# mach_xa_pin_schematic.net
KiCad netlist of a schematic drawn in Altium Designer
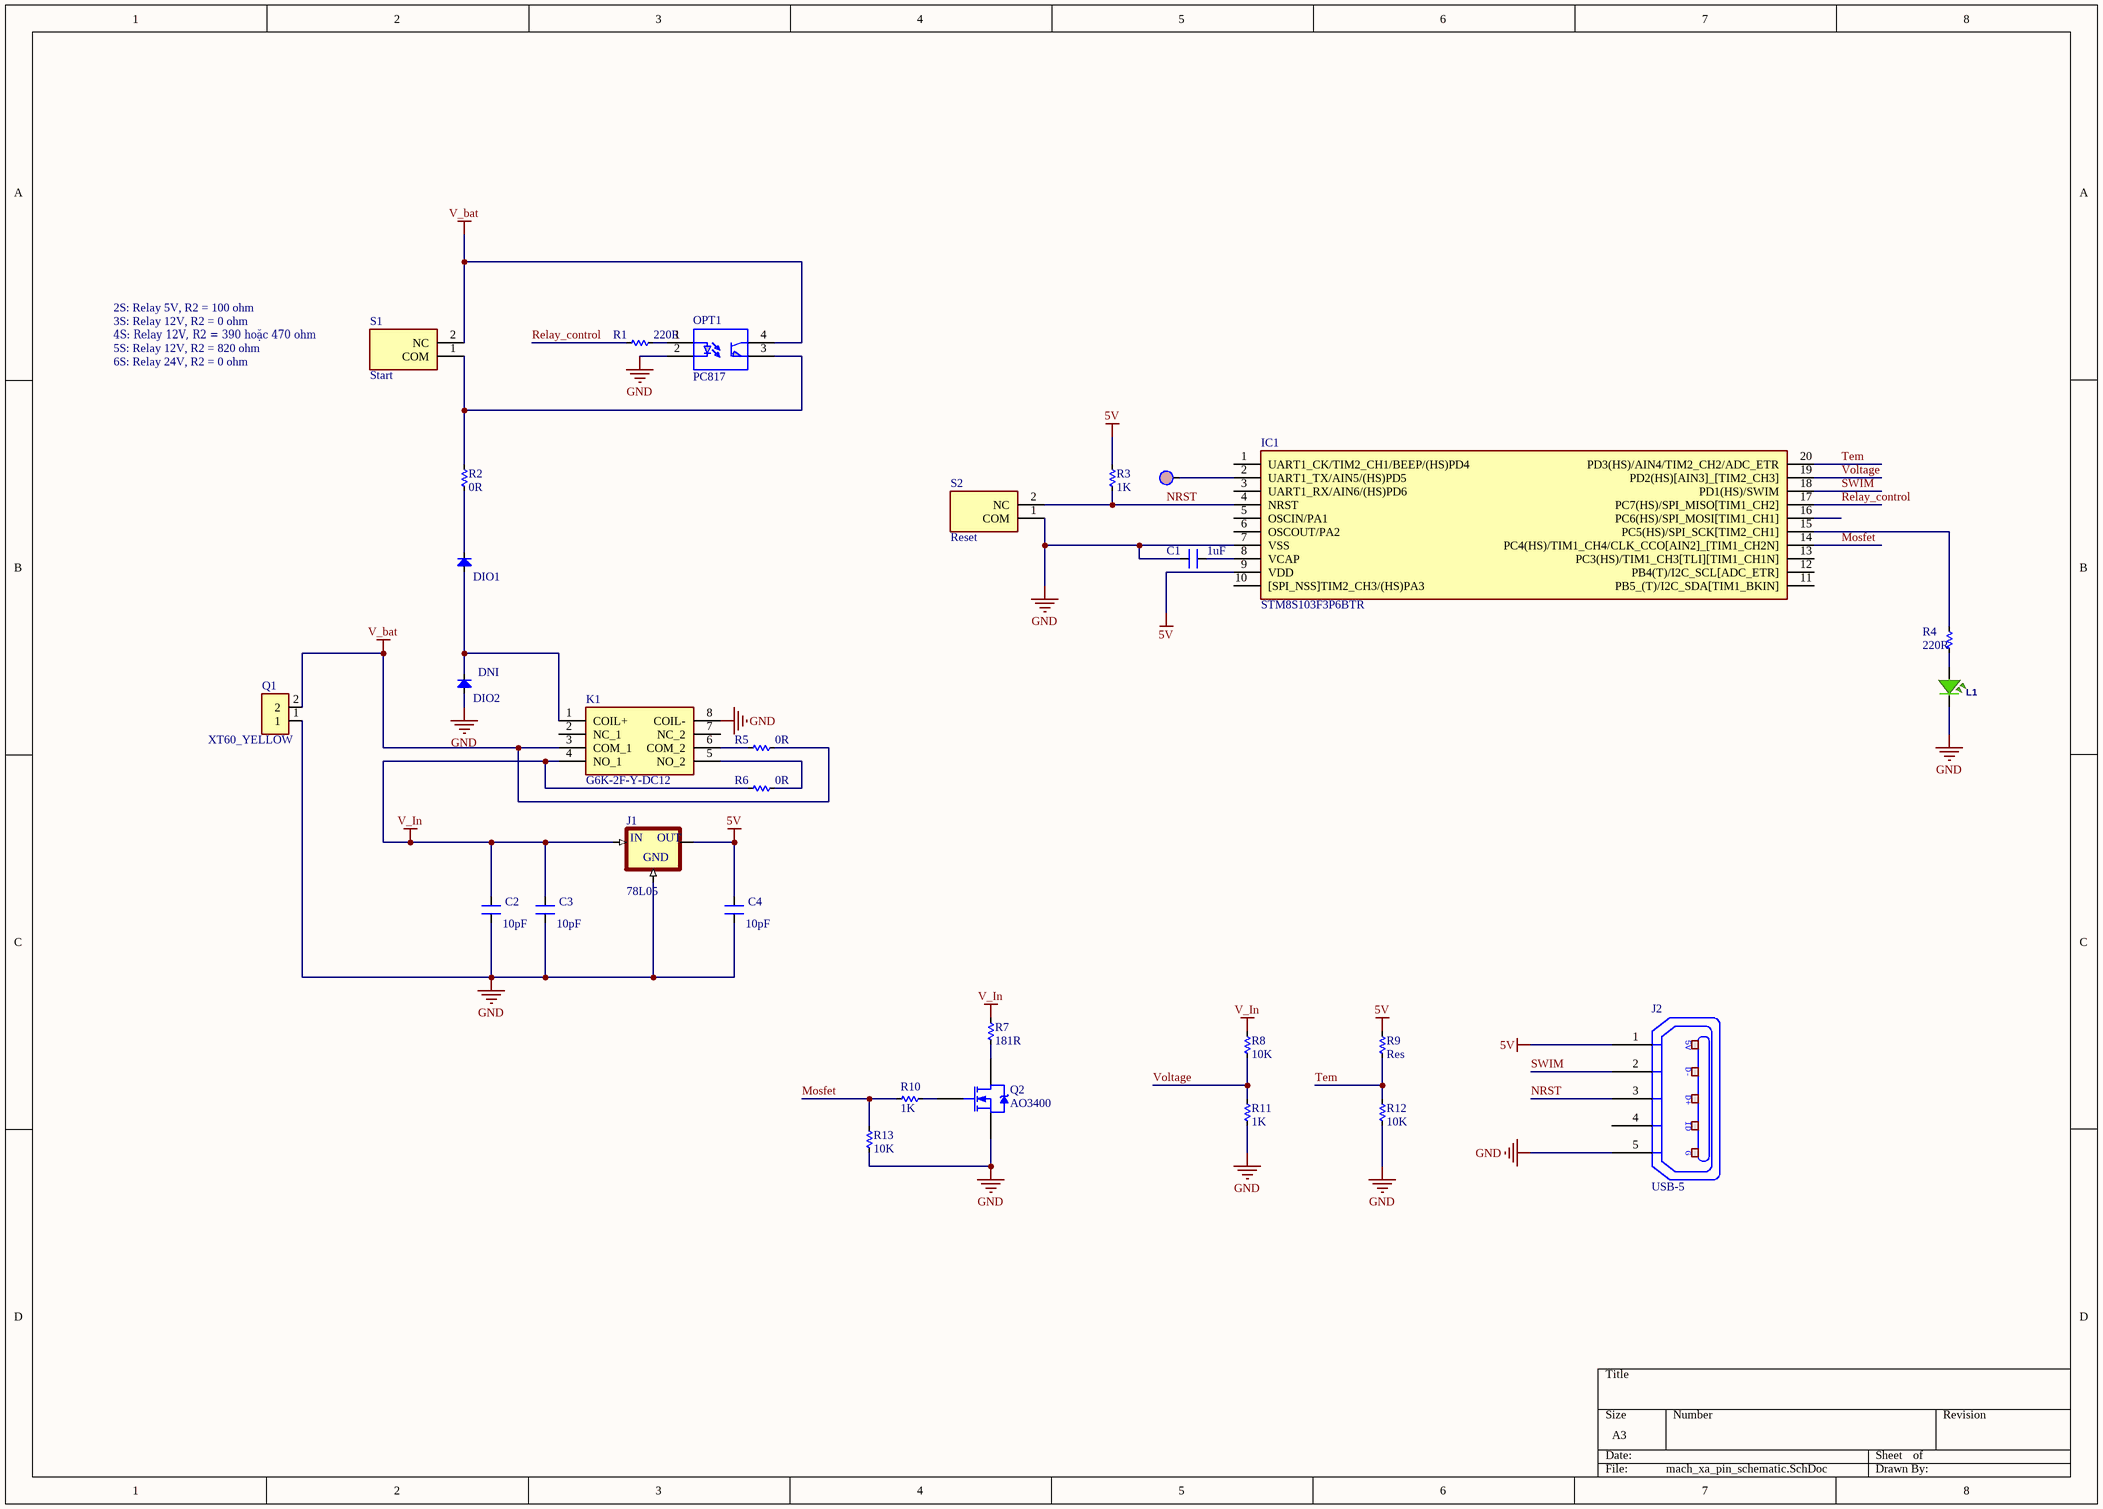
[diagram p0: mach_xa_pin_schematic.SchDoc]

(export (version "E")
  (design (tool "Eeschema 10.0.6"))
  (components
    (comp (ref "C1") (value "1uF") (footprint "CN-SMD-0603") (libsource (lib "LIBRARY") (part "CN")))
    (comp (ref "C2") (value "10pF") (footprint "CN-SMD-0603") (libsource (lib "LIBRARY") (part "CN")))
    (comp (ref "C3") (value "10pF") (footprint "CN-SMD-0603") (libsource (lib "LIBRARY") (part "CN")))
    (comp (ref "C4") (value "10pF") (footprint "CN-SMD-0603") (libsource (lib "LIBRARY") (part "CN")))
    (comp (ref "DIO1")
      (value "Diode SMD")
      (footprint "DIO-SMD-123")
      (description "Default Diode")
      (fields (field (name "PUBLISHER") "Altium Limited"))
      (libsource (lib "LIBRARY") (part "Diode SMD"))
    )
    (comp (ref "DIO2")
      (value "DNI")
      (footprint "DIO-SMD-123")
      (description "Default Diode")
      (fields (field (name "PUBLISHER") "Altium Limited"))
      (libsource (lib "LIBRARY") (part "Diode SMD"))
    )
    (comp (ref "IC1")
      (value "STM8S103F3P6BTR")
      (footprint "SamacSys:SOP65P640X120-20N")
      (description "Integrated Circuit")
      (libsource (lib "SamacSys") (part "STM8S103F3P6BTR"))
    )
    (comp (ref "J1")
      (value "78L05")
      (footprint "SOT89R:SOT89R")
      (description "IC REG LINEAR 5V 100MA SOT89-3")
      (fields (field (name "MF") "Hottech Co"))
      (libsource (lib "78L05") (part "78L05"))
    )
    (comp (ref "J2")
      (value "USB-5")
      (footprint "USB-M1")
      (fields
        (field (name "MANUFACTURER") "FCI")
        (field (name "MANUFACTURER PART NUMBER") "10118193-0001LF")
        (field (name ".CREATOR") "MM")
        (field (name ".CHECKED PCB") "RF")
        (field (name ".CHECKED SCH") "MM")
      )
      (libsource (lib "LIBRARY") (part "USB-5"))
    )
    (comp (ref "K1")
      (value "G6K-2F-Y-DC12")
      (footprint "SamacSys:G6K2FYDC12")
      (description "Relay or Contactor")
      (fields (field (name "MOUSER PART NUMBER") "653-G6K-2F-Y-DC12"))
      (libsource (lib "*") (part "G6K-2F-Y-DC12"))
    )
    (comp (ref "L1")
      (value "Led 0603 Green")
      (footprint "LED 0603 GREEN")
      (libsource (lib "VitalSignal EcgPpg Board") (part "Led 0603 Green"))
    )
    (comp (ref "OPT1")
      (value "PC817")
      (footprint "DIP-4 SMD")
      (description "OptoAcoplador 4 terminais")
      (libsource (lib "Altium_Library_Brasil") (part "PC817"))
    )
    (comp (ref "Q1")
      (value "XT60_YELLOW")
      (footprint "XT60_YELLOW:AMASS_XT60PB-M")
      (description "Power connector; 65A; PIN: 2; Colour: yellow")
      (fields (field (name "MP") "XT60 YELLOW") (field (name "MF") "Pololu"))
      (libsource (lib "XT60_YELLOW") (part "XT60_YELLOW"))
    )
    (comp (ref "Q2")
      (value "AO3400")
      (footprint "SOT-23_N")
      (description "HEXFET Power MOSFET")
      (fields (field (name "PUBLISHER") "Altium Limited"))
      (libsource (lib "IR Discrete MOSFET - Power") (part "IRLML2402"))
    )
    (comp (ref "R1")
      (value "220R")
      (footprint "RES-SMD-0603")
      (description "Resistor")
      (fields
        (field (name "MANUFACTURER") "Generic Components")
        (field (name "PUBLISHER") "Altium Hobart Technology Centre")
      )
      (libsource (lib "LIBRARY") (part "Res-SMD"))
    )
    (comp (ref "R2")
      (value "0R")
      (footprint "RES-SMD-0805")
      (description "Resistor")
      (fields
        (field (name "MANUFACTURER") "Generic Components")
        (field (name "PUBLISHER") "Altium Hobart Technology Centre")
      )
      (libsource (lib "LIBRARY") (part "Res-SMD"))
    )
    (comp (ref "R3")
      (value "1K")
      (footprint "RES-SMD-0603")
      (description "Resistor")
      (fields
        (field (name "MANUFACTURER") "Generic Components")
        (field (name "PUBLISHER") "Altium Hobart Technology Centre")
      )
      (libsource (lib "LIBRARY") (part "Res-SMD"))
    )
    (comp (ref "R4")
      (value "220R")
      (footprint "RES-SMD-0603")
      (description "Resistor")
      (fields
        (field (name "MANUFACTURER") "Generic Components")
        (field (name "PUBLISHER") "Altium Hobart Technology Centre")
      )
      (libsource (lib "LIBRARY") (part "Res-SMD"))
    )
    (comp (ref "R5")
      (value "0R")
      (footprint "RES-SMD-0201")
      (description "Resistor")
      (fields
        (field (name "MANUFACTURER") "Generic Components")
        (field (name "PUBLISHER") "Altium Hobart Technology Centre")
      )
      (libsource (lib "LIBRARY") (part "Res-SMD"))
    )
    (comp (ref "R6")
      (value "0R")
      (footprint "RES-SMD-0201")
      (description "Resistor")
      (fields
        (field (name "MANUFACTURER") "Generic Components")
        (field (name "PUBLISHER") "Altium Hobart Technology Centre")
      )
      (libsource (lib "LIBRARY") (part "Res-SMD"))
    )
    (comp (ref "R7")
      (value "181R")
      (footprint "RES-SMD-2512")
      (description "Resistor")
      (fields
        (field (name "MANUFACTURER") "Generic Components")
        (field (name "PUBLISHER") "Altium Hobart Technology Centre")
      )
      (libsource (lib "LIBRARY") (part "Res-SMD"))
    )
    (comp (ref "R8")
      (value "10K")
      (footprint "RES-SMD-0603")
      (description "Resistor")
      (fields
        (field (name "MANUFACTURER") "Generic Components")
        (field (name "PUBLISHER") "Altium Hobart Technology Centre")
      )
      (libsource (lib "LIBRARY") (part "Res-SMD"))
    )
    (comp (ref "R9")
      (value "Res")
      (footprint "RES-1/8W-SMALL-2")
      (fields
        (field (name "MANUFACTURER") "Generic Components")
        (field (name "PUBLISHER") "Altium Hobart Technology Centre")
      )
      (libsource (lib "LIBRARY") (part "Res"))
    )
    (comp (ref "R10")
      (value "1K")
      (footprint "RES-SMD-0603")
      (description "Resistor")
      (fields
        (field (name "MANUFACTURER") "Generic Components")
        (field (name "PUBLISHER") "Altium Hobart Technology Centre")
      )
      (libsource (lib "LIBRARY") (part "Res-SMD"))
    )
    (comp (ref "R11")
      (value "1K")
      (footprint "RES-SMD-0603")
      (description "Resistor")
      (fields
        (field (name "MANUFACTURER") "Generic Components")
        (field (name "PUBLISHER") "Altium Hobart Technology Centre")
      )
      (libsource (lib "LIBRARY") (part "Res-SMD"))
    )
    (comp (ref "R12")
      (value "10K")
      (footprint "RES-SMD-0603")
      (description "Resistor")
      (fields
        (field (name "MANUFACTURER") "Generic Components")
        (field (name "PUBLISHER") "Altium Hobart Technology Centre")
      )
      (libsource (lib "LIBRARY") (part "Res-SMD"))
    )
    (comp (ref "R13")
      (value "10K")
      (footprint "RES-SMD-0603")
      (description "Resistor")
      (fields
        (field (name "MANUFACTURER") "Generic Components")
        (field (name "PUBLISHER") "Altium Hobart Technology Centre")
      )
      (libsource (lib "LIBRARY") (part "Res-SMD"))
    )
    (comp (ref "S1")
      (value "Start")
      (footprint "SamacSys:TS1088R02026")
      (description "Switch")
      (fields (field (name "MANUFACTURER_PART_NUMBER") "TS-1088R-02026"))
      (libsource (lib "SamacSys") (part "TS-1088R-02026"))
    )
    (comp (ref "S2")
      (value "Reset")
      (footprint "SamacSys:TS1088R02026")
      (description "Switch")
      (fields (field (name "MANUFACTURER_PART_NUMBER") "TS-1088R-02026"))
      (libsource (lib "SamacSys") (part "TS-1088R-02026"))
    )
    (comp (ref "TP1")
      (value "TP")
      (footprint "P-TP 1MM")
      (libsource (lib "VitalSignal EcgPpg Board") (part "P-TESTPOINT"))
    )
  )
  (nets
    (net (code "1") (name "/Mosfet") (class "Default")
      (node (ref "IC1") (pin "14") (pinfunction "PC4(HS)/TIM1_CH4/CLK_CCO[AIN2]_[TIM1_CH2N]_14") (pintype "passive"))
      (node (ref "R10") (pin "1") (pinfunction "1_1") (pintype "passive"))
      (node (ref "R13") (pin "2") (pinfunction "2_2") (pintype "passive"))
    )
    (net (code "2") (name "/NRST") (class "Default")
      (node (ref "IC1") (pin "4") (pinfunction "NRST_4") (pintype "passive"))
      (node (ref "J2") (pin "3") (pinfunction "P3_3") (pintype "passive"))
      (node (ref "R3") (pin "2") (pinfunction "2_2") (pintype "passive"))
      (node (ref "S2") (pin "2") (pinfunction "NC_2") (pintype "passive"))
    )
    (net (code "3") (name "/Relay_control") (class "Default")
      (node (ref "IC1") (pin "17") (pinfunction "PC7(HS)/SPI_MISO[TIM1_CH2]_17") (pintype "passive"))
      (node (ref "R1") (pin "1") (pinfunction "1_1") (pintype "passive"))
    )
    (net (code "4") (name "/SWIM") (class "Default")
      (node (ref "IC1") (pin "18") (pinfunction "PD1(HS)/SWIM_18") (pintype "passive"))
      (node (ref "J2") (pin "2") (pinfunction "P2_2") (pintype "passive"))
    )
    (net (code "5") (name "/Tem") (class "Default")
      (node (ref "IC1") (pin "20") (pinfunction "PD3(HS)/AIN4/TIM2_CH2/ADC_ETR_20") (pintype "passive"))
      (node (ref "R12") (pin "1") (pinfunction "1_1") (pintype "passive"))
      (node (ref "R9") (pin "2") (pinfunction "2_2") (pintype "passive"))
    )
    (net (code "6") (name "/Voltage") (class "Default")
      (node (ref "IC1") (pin "19") (pinfunction "PD2(HS)[AIN3]_[TIM2_CH3]_19") (pintype "passive"))
      (node (ref "R11") (pin "1") (pinfunction "1_1") (pintype "passive"))
      (node (ref "R8") (pin "2") (pinfunction "2_2") (pintype "passive"))
    )
    (net (code "7") (name "5V") (class "Default")
      (node (ref "C4") (pin "2") (pinfunction "2_2") (pintype "passive"))
      (node (ref "IC1") (pin "9") (pinfunction "VDD_9") (pintype "passive"))
      (node (ref "J1") (pin "P$3") (pinfunction "OUT_P$3") (pintype "passive"))
      (node (ref "J2") (pin "1") (pinfunction "P1_1") (pintype "passive"))
      (node (ref "R3") (pin "1") (pinfunction "1_1") (pintype "passive"))
      (node (ref "R9") (pin "1") (pinfunction "1_1") (pintype "passive"))
    )
    (net (code "8") (name "GND") (class "Default")
      (node (ref "C1") (pin "2") (pinfunction "2_2") (pintype "passive"))
      (node (ref "C2") (pin "1") (pinfunction "1_1") (pintype "passive"))
      (node (ref "C3") (pin "1") (pinfunction "1_1") (pintype "passive"))
      (node (ref "C4") (pin "1") (pinfunction "1_1") (pintype "passive"))
      (node (ref "DIO2") (pin "1") (pinfunction "A_1") (pintype "passive"))
      (node (ref "IC1") (pin "7") (pinfunction "VSS_7") (pintype "passive"))
      (node (ref "J1") (pin "P$2") (pinfunction "GND_P$2") (pintype "input"))
      (node (ref "J2") (pin "5") (pinfunction "P5_5") (pintype "passive"))
      (node (ref "K1") (pin "8") (pinfunction "COIL-_8") (pintype "passive"))
      (node (ref "L1") (pin "2") (pinfunction "2_2") (pintype "passive"))
      (node (ref "OPT1") (pin "2") (pinfunction "K_2") (pintype "passive"))
      (node (ref "Q1") (pin "1") (pinfunction "1_1") (pintype "passive"))
      (node (ref "Q2") (pin "2") (pinfunction "S_2") (pintype "passive"))
      (node (ref "R11") (pin "2") (pinfunction "2_2") (pintype "passive"))
      (node (ref "R12") (pin "2") (pinfunction "2_2") (pintype "passive"))
      (node (ref "R13") (pin "1") (pinfunction "1_1") (pintype "passive"))
      (node (ref "S2") (pin "1") (pinfunction "COM_1") (pintype "passive"))
    )
    (net (code "9") (name "Net-(DIO1-A)") (class "Default")
      (node (ref "DIO1") (pin "1") (pinfunction "A_1") (pintype "passive"))
      (node (ref "DIO2") (pin "2") (pinfunction "K_2") (pintype "passive"))
      (node (ref "K1") (pin "1") (pinfunction "COIL+_1") (pintype "passive"))
    )
    (net (code "10") (name "Net-(DIO1-K)") (class "Default")
      (node (ref "DIO1") (pin "2") (pinfunction "K_2") (pintype "passive"))
      (node (ref "R2") (pin "2") (pinfunction "2_2") (pintype "passive"))
    )
    (net (code "11") (name "Net-(IC1-PC5(HS){slash}SPI_SCK[TIM2_CH1])") (class "Default")
      (node (ref "IC1") (pin "15") (pinfunction "PC5(HS)/SPI_SCK[TIM2_CH1]_15") (pintype "passive"))
      (node (ref "R4") (pin "1") (pinfunction "1_1") (pintype "passive"))
    )
    (net (code "12") (name "Net-(IC1-UART1_TX{slash}AIN5{slash}(HS)PD5)") (class "Default")
      (node (ref "IC1") (pin "2") (pinfunction "UART1_TX/AIN5/(HS)PD5_2") (pintype "passive"))
      (node (ref "TP1") (pin "1") (pinfunction "1_1") (pintype "passive"))
    )
    (net (code "13") (name "Net-(IC1-VCAP)") (class "Default")
      (node (ref "C1") (pin "1") (pinfunction "1_1") (pintype "passive"))
      (node (ref "IC1") (pin "8") (pinfunction "VCAP_8") (pintype "passive"))
    )
    (net (code "14") (name "Net-(K1-COM_2)") (class "Default")
      (node (ref "K1") (pin "6") (pinfunction "COM_2_6") (pintype "passive"))
      (node (ref "R5") (pin "2") (pinfunction "2_2") (pintype "passive"))
    )
    (net (code "15") (name "Net-(K1-NO_2)") (class "Default")
      (node (ref "K1") (pin "5") (pinfunction "NO_2_5") (pintype "passive"))
      (node (ref "R6") (pin "1") (pinfunction "1_1") (pintype "passive"))
    )
    (net (code "16") (name "Net-(L1-Pad1)") (class "Default")
      (node (ref "L1") (pin "1") (pinfunction "1_1") (pintype "passive"))
      (node (ref "R4") (pin "2") (pinfunction "2_2") (pintype "passive"))
    )
    (net (code "17") (name "Net-(OPT1-A)") (class "Default")
      (node (ref "OPT1") (pin "1") (pinfunction "A_1") (pintype "passive"))
      (node (ref "R1") (pin "2") (pinfunction "2_2") (pintype "passive"))
    )
    (net (code "18") (name "Net-(OPT1-EMISSOR)") (class "Default")
      (node (ref "OPT1") (pin "3") (pinfunction "EMISSOR_3") (pintype "passive"))
      (node (ref "R2") (pin "1") (pinfunction "1_1") (pintype "passive"))
      (node (ref "S1") (pin "1") (pinfunction "COM_1") (pintype "passive"))
    )
    (net (code "19") (name "Net-(Q2-D)") (class "Default")
      (node (ref "Q2") (pin "3") (pinfunction "D_3") (pintype "passive"))
      (node (ref "R7") (pin "2") (pinfunction "2_2") (pintype "passive"))
    )
    (net (code "20") (name "Net-(Q2-G)") (class "Default")
      (node (ref "Q2") (pin "1") (pinfunction "G_1") (pintype "passive"))
      (node (ref "R10") (pin "2") (pinfunction "2_2") (pintype "passive"))
    )
    (net (code "21") (name "V_In") (class "Default")
      (node (ref "C2") (pin "2") (pinfunction "2_2") (pintype "passive"))
      (node (ref "C3") (pin "2") (pinfunction "2_2") (pintype "passive"))
      (node (ref "J1") (pin "P$1") (pinfunction "IN_P$1") (pintype "input"))
      (node (ref "K1") (pin "4") (pinfunction "NO_1_4") (pintype "passive"))
      (node (ref "R6") (pin "2") (pinfunction "2_2") (pintype "passive"))
      (node (ref "R7") (pin "1") (pinfunction "1_1") (pintype "passive"))
      (node (ref "R8") (pin "1") (pinfunction "1_1") (pintype "passive"))
    )
    (net (code "22") (name "V_bat") (class "Default")
      (node (ref "K1") (pin "3") (pinfunction "COM_1_3") (pintype "passive"))
      (node (ref "OPT1") (pin "4") (pinfunction "COLETOR_4") (pintype "passive"))
      (node (ref "Q1") (pin "2") (pinfunction "2_2") (pintype "passive"))
      (node (ref "R5") (pin "1") (pinfunction "1_1") (pintype "passive"))
      (node (ref "S1") (pin "2") (pinfunction "NC_2") (pintype "passive"))
    )
    (net (code "23") (name "unconnected-(IC1-OSCIN{slash}PA1-Pad5)") (class "Default")
      (node (ref "IC1") (pin "5") (pinfunction "OSCIN/PA1_5") (pintype "passive"))
    )
    (net (code "24") (name "unconnected-(IC1-OSCOUT{slash}PA2-Pad6)") (class "Default")
      (node (ref "IC1") (pin "6") (pinfunction "OSCOUT/PA2_6") (pintype "passive"))
    )
    (net (code "25") (name "unconnected-(IC1-PB4(T){slash}I2C_SCL[ADC_ETR]-Pad12)") (class "Default")
      (node (ref "IC1") (pin "12") (pinfunction "PB4(T)/I2C_SCL[ADC_ETR]_12") (pintype "passive"))
    )
    (net (code "26") (name "unconnected-(IC1-PB5_(T){slash}I2C_SDA[TIM1_BKIN]-Pad11)") (class "Default")
      (node (ref "IC1") (pin "11") (pinfunction "PB5_(T)/I2C_SDA[TIM1_BKIN]_11") (pintype "passive"))
    )
    (net (code "27") (name "unconnected-(IC1-PC3(HS){slash}TIM1_CH3[TLI][TIM1_CH1N]-Pad13)") (class "Default")
      (node (ref "IC1") (pin "13") (pinfunction "PC3(HS)/TIM1_CH3[TLI][TIM1_CH1N]_13") (pintype "passive"))
    )
    (net (code "28") (name "unconnected-(IC1-PC6(HS){slash}SPI_MOSI[TIM1_CH1]-Pad16)") (class "Default")
      (node (ref "IC1") (pin "16") (pinfunction "PC6(HS)/SPI_MOSI[TIM1_CH1]_16") (pintype "passive"))
    )
    (net (code "29") (name "unconnected-(IC1-UART1_CK{slash}TIM2_CH1{slash}BEEP{slash}(HS)PD4-Pad1)") (class "Default")
      (node (ref "IC1") (pin "1") (pinfunction "UART1_CK/TIM2_CH1/BEEP/(HS)PD4_1") (pintype "passive"))
    )
    (net (code "30") (name "unconnected-(IC1-UART1_RX{slash}AIN6{slash}(HS)PD6-Pad3)") (class "Default")
      (node (ref "IC1") (pin "3") (pinfunction "UART1_RX/AIN6/(HS)PD6_3") (pintype "passive"))
    )
    (net (code "31") (name "unconnected-(IC1-[SPI_NSS]TIM2_CH3{slash}(HS)PA3-Pad10)") (class "Default")
      (node (ref "IC1") (pin "10") (pinfunction "[SPI_NSS]TIM2_CH3/(HS)PA3_10") (pintype "passive"))
    )
    (net (code "32") (name "unconnected-(J2-P4-Pad4)") (class "Default")
      (node (ref "J2") (pin "4") (pinfunction "P4_4") (pintype "passive"))
    )
    (net (code "33") (name "unconnected-(K1-NC_1-Pad2)") (class "Default")
      (node (ref "K1") (pin "2") (pinfunction "NC_1_2") (pintype "passive"))
    )
    (net (code "34") (name "unconnected-(K1-NC_2-Pad7)") (class "Default")
      (node (ref "K1") (pin "7") (pinfunction "NC_2_7") (pintype "passive"))
    )
  )
)
